# pirFadeDC.net
KiCad netlist of a schematic drawn in EAGLE
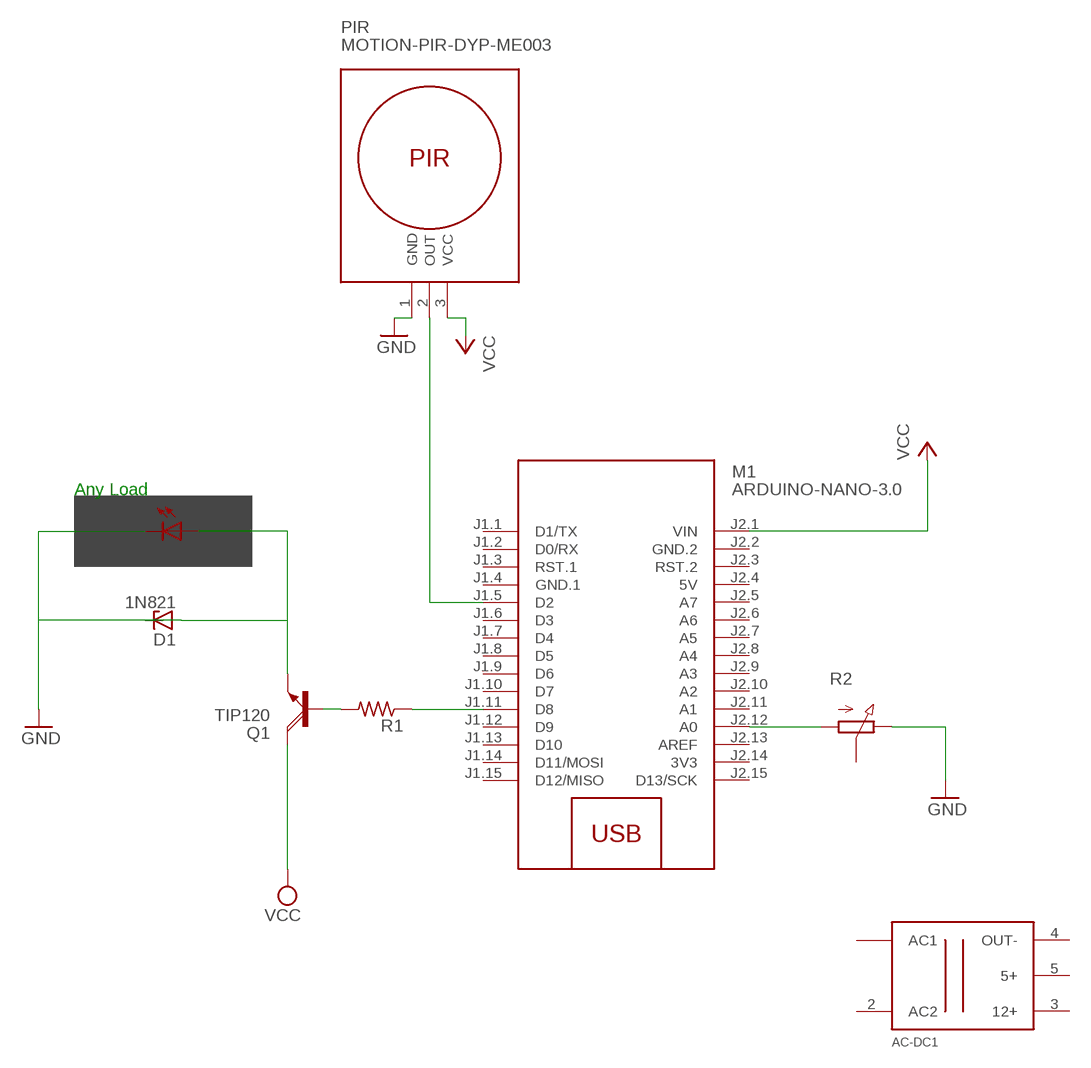
[diagram p0: schematic, sheet 1]

(export (version "E")
  (design (tool "Eeschema 10.0.6"))
  (components
    (comp (ref "AC-DC1")
      (value "GENERIC_AC/DC")
      (footprint "eagle-import:AC_DC")
      (libsource (lib "eagle-import") (part "GENERIC_AC/DC"))
    )
    (comp (ref "D1")
      (value "1N821")
      (footprint "eagle-import:DO35Z10")
      (libsource (lib "eagle-import") (part "1N821"))
    )
    (comp (ref "LED1")
      (value "LED_ELD260")
      (footprint "eagle-import:LED_LD260")
      (libsource (lib "eagle-import") (part "LED_ELD260"))
    )
    (comp (ref "M1")
      (value "ARDUINO-NANO-3.0")
      (footprint "eagle-import:ARDUINO-NANO-3.0")
      (libsource (lib "eagle-import") (part "ARDUINO-NANO-3.0"))
    )
    (comp (ref "PIR")
      (value "MOTION-PIR-DYP-ME003")
      (footprint "eagle-import:MOTION-PIR-DYP-ME003")
      (libsource (lib "eagle-import") (part "MOTION-PIR-DYP-ME003"))
    )
    (comp (ref "Q1")
      (value "TIP120")
      (footprint "eagle-import:TO220AH")
      (libsource (lib "eagle-import") (part "TIP120"))
    )
    (comp (ref "R1")
      (value "FLIPFLOP-RES")
      (footprint "eagle-import:0805-THM")
      (libsource (lib "eagle-import") (part "FLIPFLOP-RES"))
    )
    (comp (ref "R2")
      (value "PC25")
      (footprint "eagle-import:PC25")
      (fields (field (name "MF") "CLAROSTAT") (field (name "MPN") "308NPC25KS"))
      (libsource (lib "eagle-import") (part "PC25"))
    )
  )
  (nets
    (net (code "1") (name "/3V3") (class "Default")
      (node (ref "M1") (pin "J2.14") (pinfunction "3V3_J2.14") (pintype "power_in"))
    )
    (net (code "2") (name "/5V") (class "Default")
      (node (ref "M1") (pin "J2.4") (pinfunction "5V_J2.4") (pintype "power_in"))
    )
    (net (code "3") (name "/GND.1") (class "Default")
      (node (ref "M1") (pin "J1.4") (pinfunction "GND.1_J1.4") (pintype "power_in"))
    )
    (net (code "4") (name "/GND.2") (class "Default")
      (node (ref "M1") (pin "J2.2") (pinfunction "GND.2_J2.2") (pintype "power_in"))
    )
    (net (code "5") (name "GND") (class "Default")
      (node (ref "D1") (pin "A") (pinfunction "A_A") (pintype "passive"))
      (node (ref "D1") (pin "C") (pinfunction "C_C") (pintype "passive"))
      (node (ref "LED1") (pin "A") (pinfunction "A_A") (pintype "passive"))
      (node (ref "LED1") (pin "K") (pinfunction "C_K") (pintype "passive"))
      (node (ref "PIR") (pin "1") (pinfunction "GND_1") (pintype "power_in"))
      (node (ref "Q1") (pin "E") (pinfunction "E_E") (pintype "passive"))
      (node (ref "R2") (pin "E") (pinfunction "E_E") (pintype "passive"))
    )
    (net (code "6") (name "Net-(M1-A0)") (class "Default")
      (node (ref "M1") (pin "J2.12") (pinfunction "A0_J2.12") (pintype "bidirectional"))
      (node (ref "R2") (pin "A") (pinfunction "A_A") (pintype "passive"))
    )
    (net (code "7") (name "Net-(M1-D2)") (class "Default")
      (node (ref "M1") (pin "J1.5") (pinfunction "D2_J1.5") (pintype "bidirectional"))
      (node (ref "PIR") (pin "2") (pinfunction "OUT_2") (pintype "output"))
    )
    (net (code "8") (name "Net-(M1-D8)") (class "Default")
      (node (ref "M1") (pin "J1.11") (pinfunction "D8_J1.11") (pintype "bidirectional"))
      (node (ref "R1") (pin "1") (pinfunction "1_1") (pintype "passive"))
    )
    (net (code "9") (name "Net-(Q1-PadB)") (class "Default")
      (node (ref "Q1") (pin "B") (pinfunction "B_B") (pintype "passive"))
      (node (ref "R1") (pin "2") (pinfunction "2_2") (pintype "passive"))
    )
    (net (code "10") (name "VCC") (class "Default")
      (node (ref "M1") (pin "J2.1") (pinfunction "VIN_J2.1") (pintype "power_in"))
      (node (ref "PIR") (pin "3") (pinfunction "VCC_3") (pintype "power_in"))
      (node (ref "Q1") (pin "C") (pinfunction "C_C") (pintype "passive"))
    )
    (net (code "11") (name "unconnected-(AC-DC1-5+-Pad5)") (class "Default")
      (node (ref "AC-DC1") (pin "5") (pinfunction "5+_5") (pintype "bidirectional"))
    )
    (net (code "12") (name "unconnected-(AC-DC1-12+-Pad3)") (class "Default")
      (node (ref "AC-DC1") (pin "3") (pinfunction "12+_3") (pintype "output"))
    )
    (net (code "13") (name "unconnected-(AC-DC1-AC1-Pad1)") (class "Default")
      (node (ref "AC-DC1") (pin "1") (pinfunction "AC1_1") (pintype "input"))
    )
    (net (code "14") (name "unconnected-(AC-DC1-AC2-Pad2)") (class "Default")
      (node (ref "AC-DC1") (pin "2") (pinfunction "AC2_2") (pintype "input"))
    )
    (net (code "15") (name "unconnected-(AC-DC1-OUT--Pad4)") (class "Default")
      (node (ref "AC-DC1") (pin "4") (pinfunction "OUT-_4") (pintype "output"))
    )
    (net (code "16") (name "unconnected-(M1-A1-PadJ2.11)") (class "Default")
      (node (ref "M1") (pin "J2.11") (pinfunction "A1_J2.11") (pintype "bidirectional"))
    )
    (net (code "17") (name "unconnected-(M1-A2-PadJ2.10)") (class "Default")
      (node (ref "M1") (pin "J2.10") (pinfunction "A2_J2.10") (pintype "bidirectional"))
    )
    (net (code "18") (name "unconnected-(M1-A3-PadJ2.9)") (class "Default")
      (node (ref "M1") (pin "J2.9") (pinfunction "A3_J2.9") (pintype "bidirectional"))
    )
    (net (code "19") (name "unconnected-(M1-A4-PadJ2.8)") (class "Default")
      (node (ref "M1") (pin "J2.8") (pinfunction "A4_J2.8") (pintype "bidirectional"))
    )
    (net (code "20") (name "unconnected-(M1-A5-PadJ2.7)") (class "Default")
      (node (ref "M1") (pin "J2.7") (pinfunction "A5_J2.7") (pintype "bidirectional"))
    )
    (net (code "21") (name "unconnected-(M1-A6-PadJ2.6)") (class "Default")
      (node (ref "M1") (pin "J2.6") (pinfunction "A6_J2.6") (pintype "bidirectional"))
    )
    (net (code "22") (name "unconnected-(M1-A7-PadJ2.5)") (class "Default")
      (node (ref "M1") (pin "J2.5") (pinfunction "A7_J2.5") (pintype "bidirectional"))
    )
    (net (code "23") (name "unconnected-(M1-AREF-PadJ2.13)") (class "Default")
      (node (ref "M1") (pin "J2.13") (pinfunction "AREF_J2.13") (pintype "bidirectional"))
    )
    (net (code "24") (name "unconnected-(M1-D0{slash}RX-PadJ1.2)") (class "Default")
      (node (ref "M1") (pin "J1.2") (pinfunction "D0/RX_J1.2") (pintype "bidirectional"))
    )
    (net (code "25") (name "unconnected-(M1-D1{slash}TX-PadJ1.1)") (class "Default")
      (node (ref "M1") (pin "J1.1") (pinfunction "D1/TX_J1.1") (pintype "bidirectional"))
    )
    (net (code "26") (name "unconnected-(M1-D3-PadJ1.6)") (class "Default")
      (node (ref "M1") (pin "J1.6") (pinfunction "D3_J1.6") (pintype "bidirectional"))
    )
    (net (code "27") (name "unconnected-(M1-D4-PadJ1.7)") (class "Default")
      (node (ref "M1") (pin "J1.7") (pinfunction "D4_J1.7") (pintype "bidirectional"))
    )
    (net (code "28") (name "unconnected-(M1-D5-PadJ1.8)") (class "Default")
      (node (ref "M1") (pin "J1.8") (pinfunction "D5_J1.8") (pintype "bidirectional"))
    )
    (net (code "29") (name "unconnected-(M1-D6-PadJ1.9)") (class "Default")
      (node (ref "M1") (pin "J1.9") (pinfunction "D6_J1.9") (pintype "bidirectional"))
    )
    (net (code "30") (name "unconnected-(M1-D7-PadJ1.10)") (class "Default")
      (node (ref "M1") (pin "J1.10") (pinfunction "D7_J1.10") (pintype "bidirectional"))
    )
    (net (code "31") (name "unconnected-(M1-D9-PadJ1.12)") (class "Default")
      (node (ref "M1") (pin "J1.12") (pinfunction "D9_J1.12") (pintype "bidirectional"))
    )
    (net (code "32") (name "unconnected-(M1-D10-PadJ1.13)") (class "Default")
      (node (ref "M1") (pin "J1.13") (pinfunction "D10_J1.13") (pintype "bidirectional"))
    )
    (net (code "33") (name "unconnected-(M1-D11{slash}MOSI-PadJ1.14)") (class "Default")
      (node (ref "M1") (pin "J1.14") (pinfunction "D11/MOSI_J1.14") (pintype "bidirectional"))
    )
    (net (code "34") (name "unconnected-(M1-D12{slash}MISO-PadJ1.15)") (class "Default")
      (node (ref "M1") (pin "J1.15") (pinfunction "D12/MISO_J1.15") (pintype "bidirectional"))
    )
    (net (code "35") (name "unconnected-(M1-D13{slash}SCK-PadJ2.15)") (class "Default")
      (node (ref "M1") (pin "J2.15") (pinfunction "D13/SCK_J2.15") (pintype "bidirectional"))
    )
    (net (code "36") (name "unconnected-(M1-RST.1-PadJ1.3)") (class "Default")
      (node (ref "M1") (pin "J1.3") (pinfunction "RST.1_J1.3") (pintype "bidirectional"))
    )
    (net (code "37") (name "unconnected-(M1-RST.2-PadJ2.3)") (class "Default")
      (node (ref "M1") (pin "J2.3") (pinfunction "RST.2_J2.3") (pintype "bidirectional"))
    )
    (net (code "38") (name "unconnected-(R2-PadS)") (class "Default")
      (node (ref "R2") (pin "S") (pinfunction "S_S") (pintype "passive"))
    )
  )
)
